# WW-12-fixture.net
KiCad netlist of a schematic drawn in EAGLE
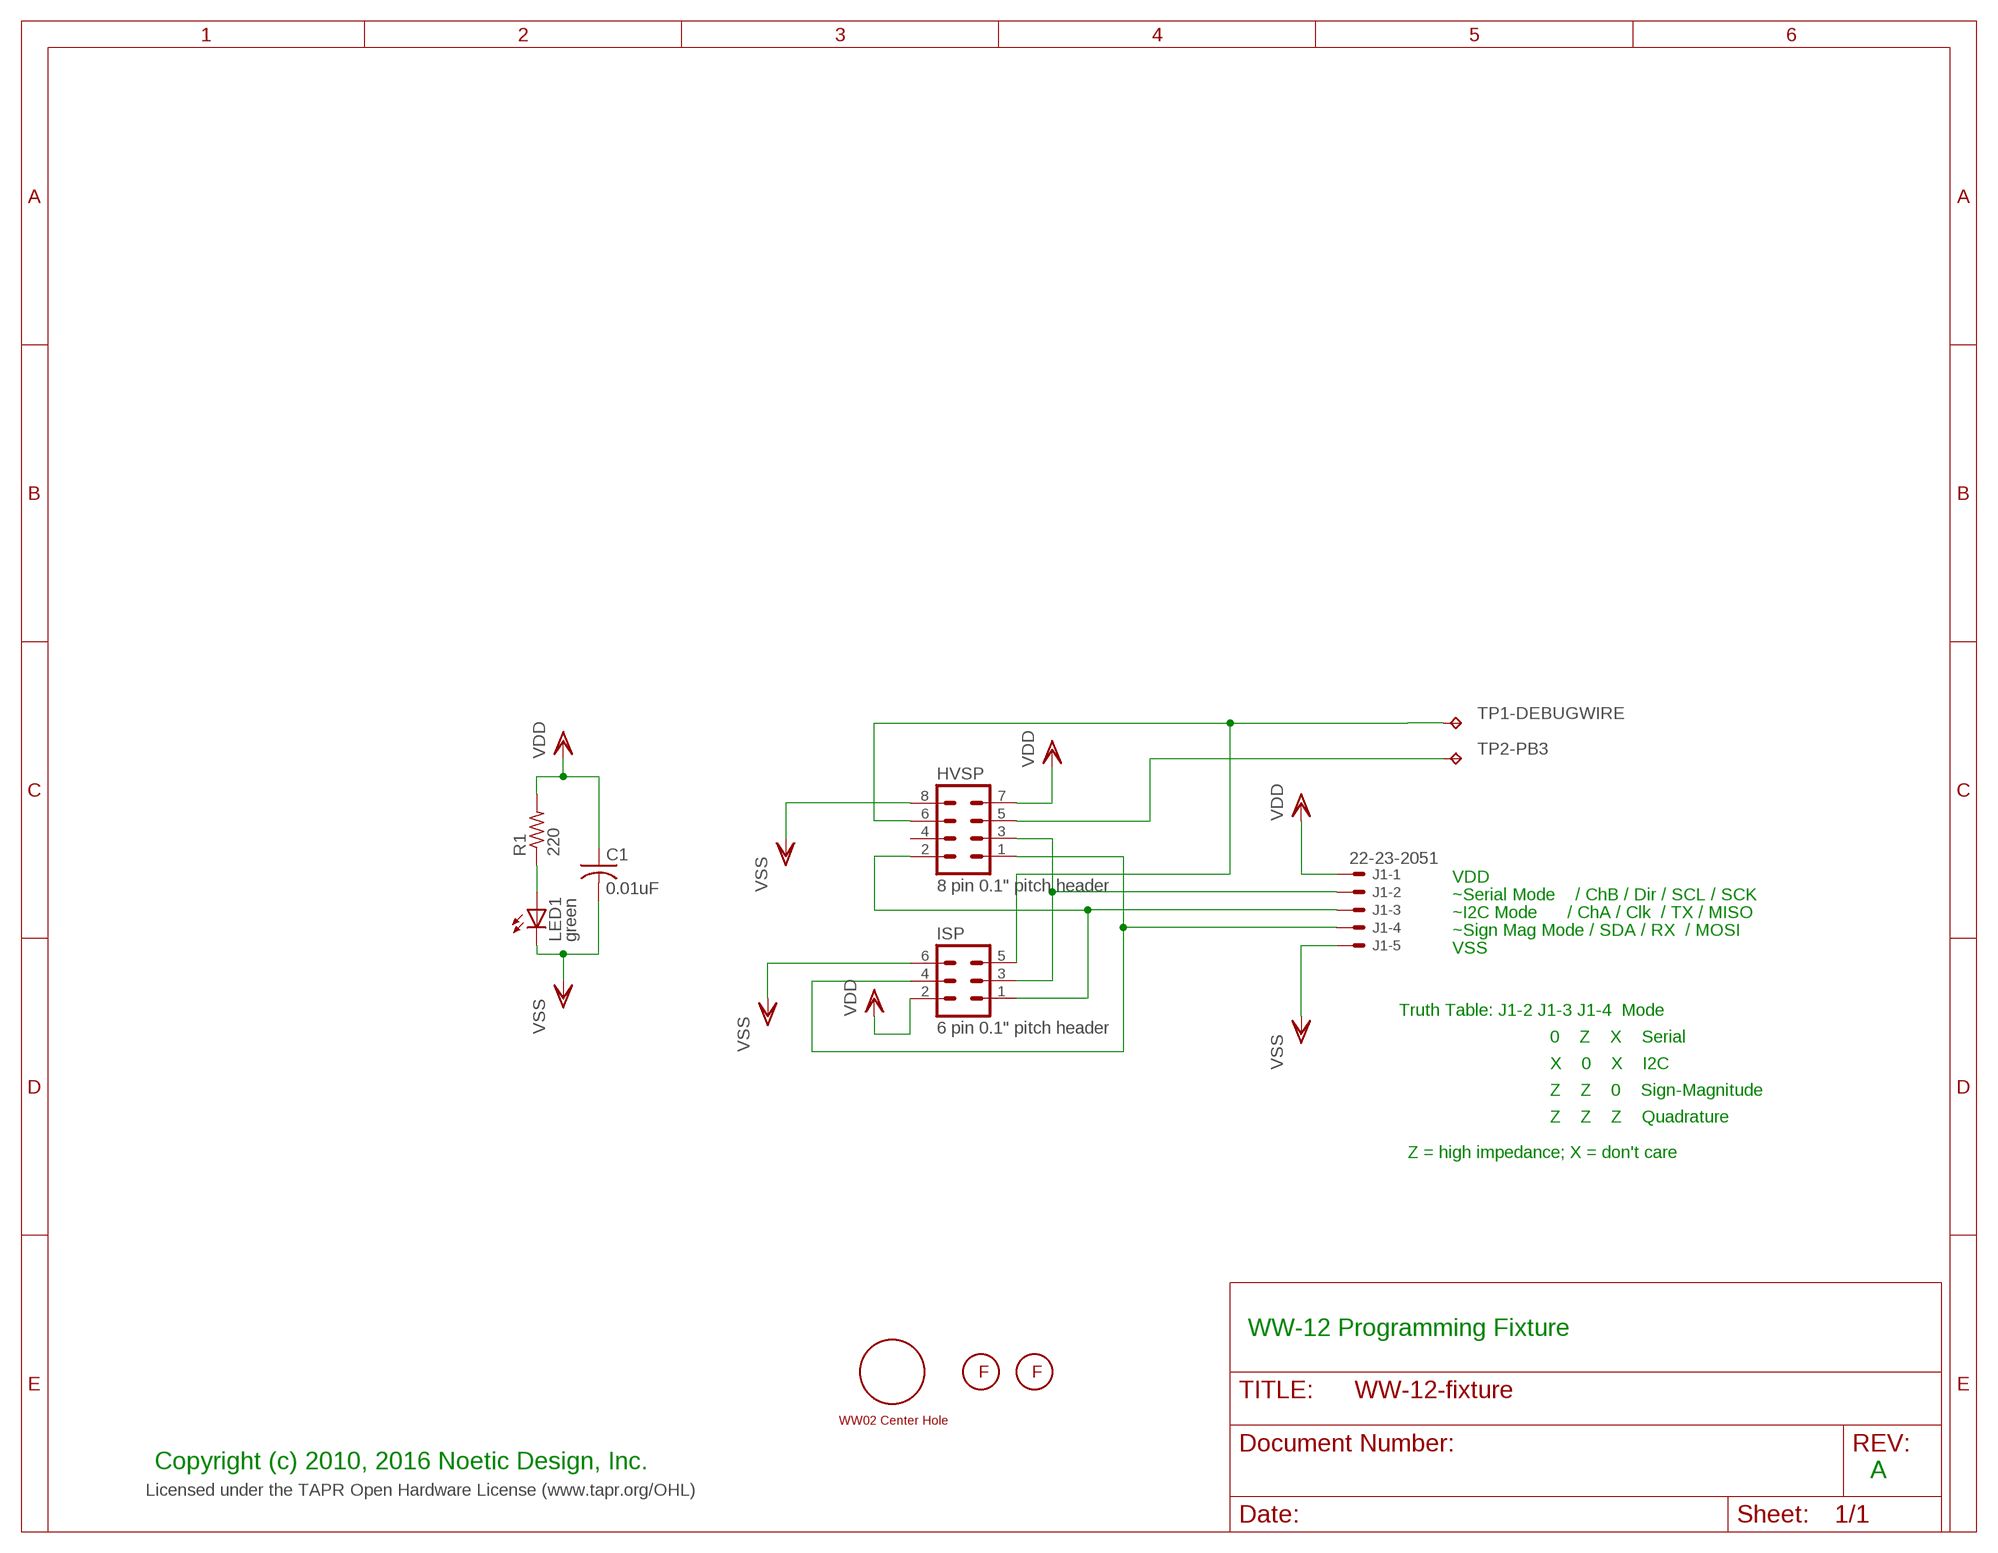
[diagram p0: schematic, sheet 1]

(export (version "E")
  (design (tool "Eeschema 10.0.6"))
  (components
    (comp (ref "C1")
      (value "0.01uF")
      (footprint "eagle-import:C0603")
      (libsource (lib "eagle-import") (part "C-USC0603"))
    )
    (comp (ref "FM1")
      (value "FIDUCIAL2MMCIRCLE")
      (footprint "eagle-import:FIDUCIAL_2MMCIRCLE")
      (libsource (lib "eagle-import") (part "FIDUCIAL2MMCIRCLE"))
    )
    (comp (ref "FM2")
      (value "FIDUCIAL2MMCIRCLE")
      (footprint "eagle-import:FIDUCIAL_2MMCIRCLE")
      (libsource (lib "eagle-import") (part "FIDUCIAL2MMCIRCLE"))
    )
    (comp (ref "HVSP")
      (value "8 pin 0.1\" pitch header")
      (footprint "eagle-import:MA04-2")
      (libsource (lib "eagle-import") (part "MA04-2"))
    )
    (comp (ref "ISP")
      (value "6 pin 0.1\" pitch header")
      (footprint "eagle-import:MA03-2")
      (libsource (lib "eagle-import") (part "MA03-2"))
    )
    (comp (ref "J1")
      (value "22-23-2051")
      (footprint "eagle-import:22-23-2051")
      (libsource (lib "eagle-import") (part "22-23-2051"))
    )
    (comp (ref "LED1")
      (value "green")
      (footprint "eagle-import:CHIP-LED0603")
      (libsource (lib "eagle-import") (part "LEDCHIP-LED0603"))
    )
    (comp (ref "R1")
      (value "220")
      (footprint "eagle-import:R0603")
      (libsource (lib "eagle-import") (part "R-US_R0603"))
    )
    (comp (ref "TP1-DEBUGWIRE")
      (value "DEBUG WIRE")
      (footprint "eagle-import:B1,27")
      (libsource (lib "eagle-import") (part "TPB1,27"))
    )
    (comp (ref "TP2-PB3")
      (value "DEBUG WIRE")
      (footprint "eagle-import:B1,27")
      (libsource (lib "eagle-import") (part "TPB1,27"))
    )
    (comp (ref "U$1")
      (value "WW02-CENTER")
      (footprint "eagle-import:WW02-CENTER")
      (libsource (lib "eagle-import") (part "WW02-CENTER"))
    )
  )
  (nets
    (net (code "1") (name "Net-(HVSP-Pad5)") (class "Default")
      (node (ref "HVSP") (pin "5") (pinfunction "5_5") (pintype "passive"))
      (node (ref "TP2-PB3") (pin "TP") (pinfunction "TP_TP") (pintype "input"))
    )
    (net (code "2") (name "Net-(HVSP-Pad6)") (class "Default")
      (node (ref "HVSP") (pin "6") (pinfunction "6_6") (pintype "passive"))
      (node (ref "ISP") (pin "5") (pinfunction "5_5") (pintype "passive"))
      (node (ref "TP1-DEBUGWIRE") (pin "TP") (pinfunction "TP_TP") (pintype "input"))
    )
    (net (code "3") (name "Net-(J1B-S)") (class "Default")
      (node (ref "HVSP") (pin "3") (pinfunction "3_3") (pintype "passive"))
      (node (ref "ISP") (pin "3") (pinfunction "3_3") (pintype "passive"))
      (node (ref "J1") (pin "2") (pinfunction "S_2") (pintype "passive"))
    )
    (net (code "4") (name "Net-(J1C-S)") (class "Default")
      (node (ref "HVSP") (pin "2") (pinfunction "2_2") (pintype "passive"))
      (node (ref "ISP") (pin "1") (pinfunction "1_1") (pintype "passive"))
      (node (ref "J1") (pin "3") (pinfunction "S_3") (pintype "passive"))
    )
    (net (code "5") (name "Net-(J1D-S)") (class "Default")
      (node (ref "HVSP") (pin "1") (pinfunction "1_1") (pintype "passive"))
      (node (ref "ISP") (pin "4") (pinfunction "4_4") (pintype "passive"))
      (node (ref "J1") (pin "4") (pinfunction "S_4") (pintype "passive"))
    )
    (net (code "6") (name "Net-(LED1-PadA)") (class "Default")
      (node (ref "LED1") (pin "A") (pinfunction "A_A") (pintype "passive"))
      (node (ref "R1") (pin "1") (pinfunction "1_1") (pintype "passive"))
    )
    (net (code "7") (name "VDD") (class "Default")
      (node (ref "C1") (pin "1") (pinfunction "1_1") (pintype "passive"))
      (node (ref "HVSP") (pin "7") (pinfunction "7_7") (pintype "passive"))
      (node (ref "ISP") (pin "2") (pinfunction "2_2") (pintype "passive"))
      (node (ref "J1") (pin "1") (pinfunction "S_1") (pintype "passive"))
      (node (ref "R1") (pin "2") (pinfunction "2_2") (pintype "passive"))
    )
    (net (code "8") (name "VSS") (class "Default")
      (node (ref "C1") (pin "2") (pinfunction "2_2") (pintype "passive"))
      (node (ref "HVSP") (pin "8") (pinfunction "8_8") (pintype "passive"))
      (node (ref "ISP") (pin "6") (pinfunction "6_6") (pintype "passive"))
      (node (ref "J1") (pin "5") (pinfunction "S_5") (pintype "passive"))
      (node (ref "LED1") (pin "C") (pinfunction "C_C") (pintype "passive"))
    )
    (net (code "9") (name "unconnected-(HVSP-Pad4)") (class "Default")
      (node (ref "HVSP") (pin "4") (pinfunction "4_4") (pintype "passive"))
    )
  )
)
